# FPSInterface.net
KiCad netlist of a schematic drawn in Altium Designer
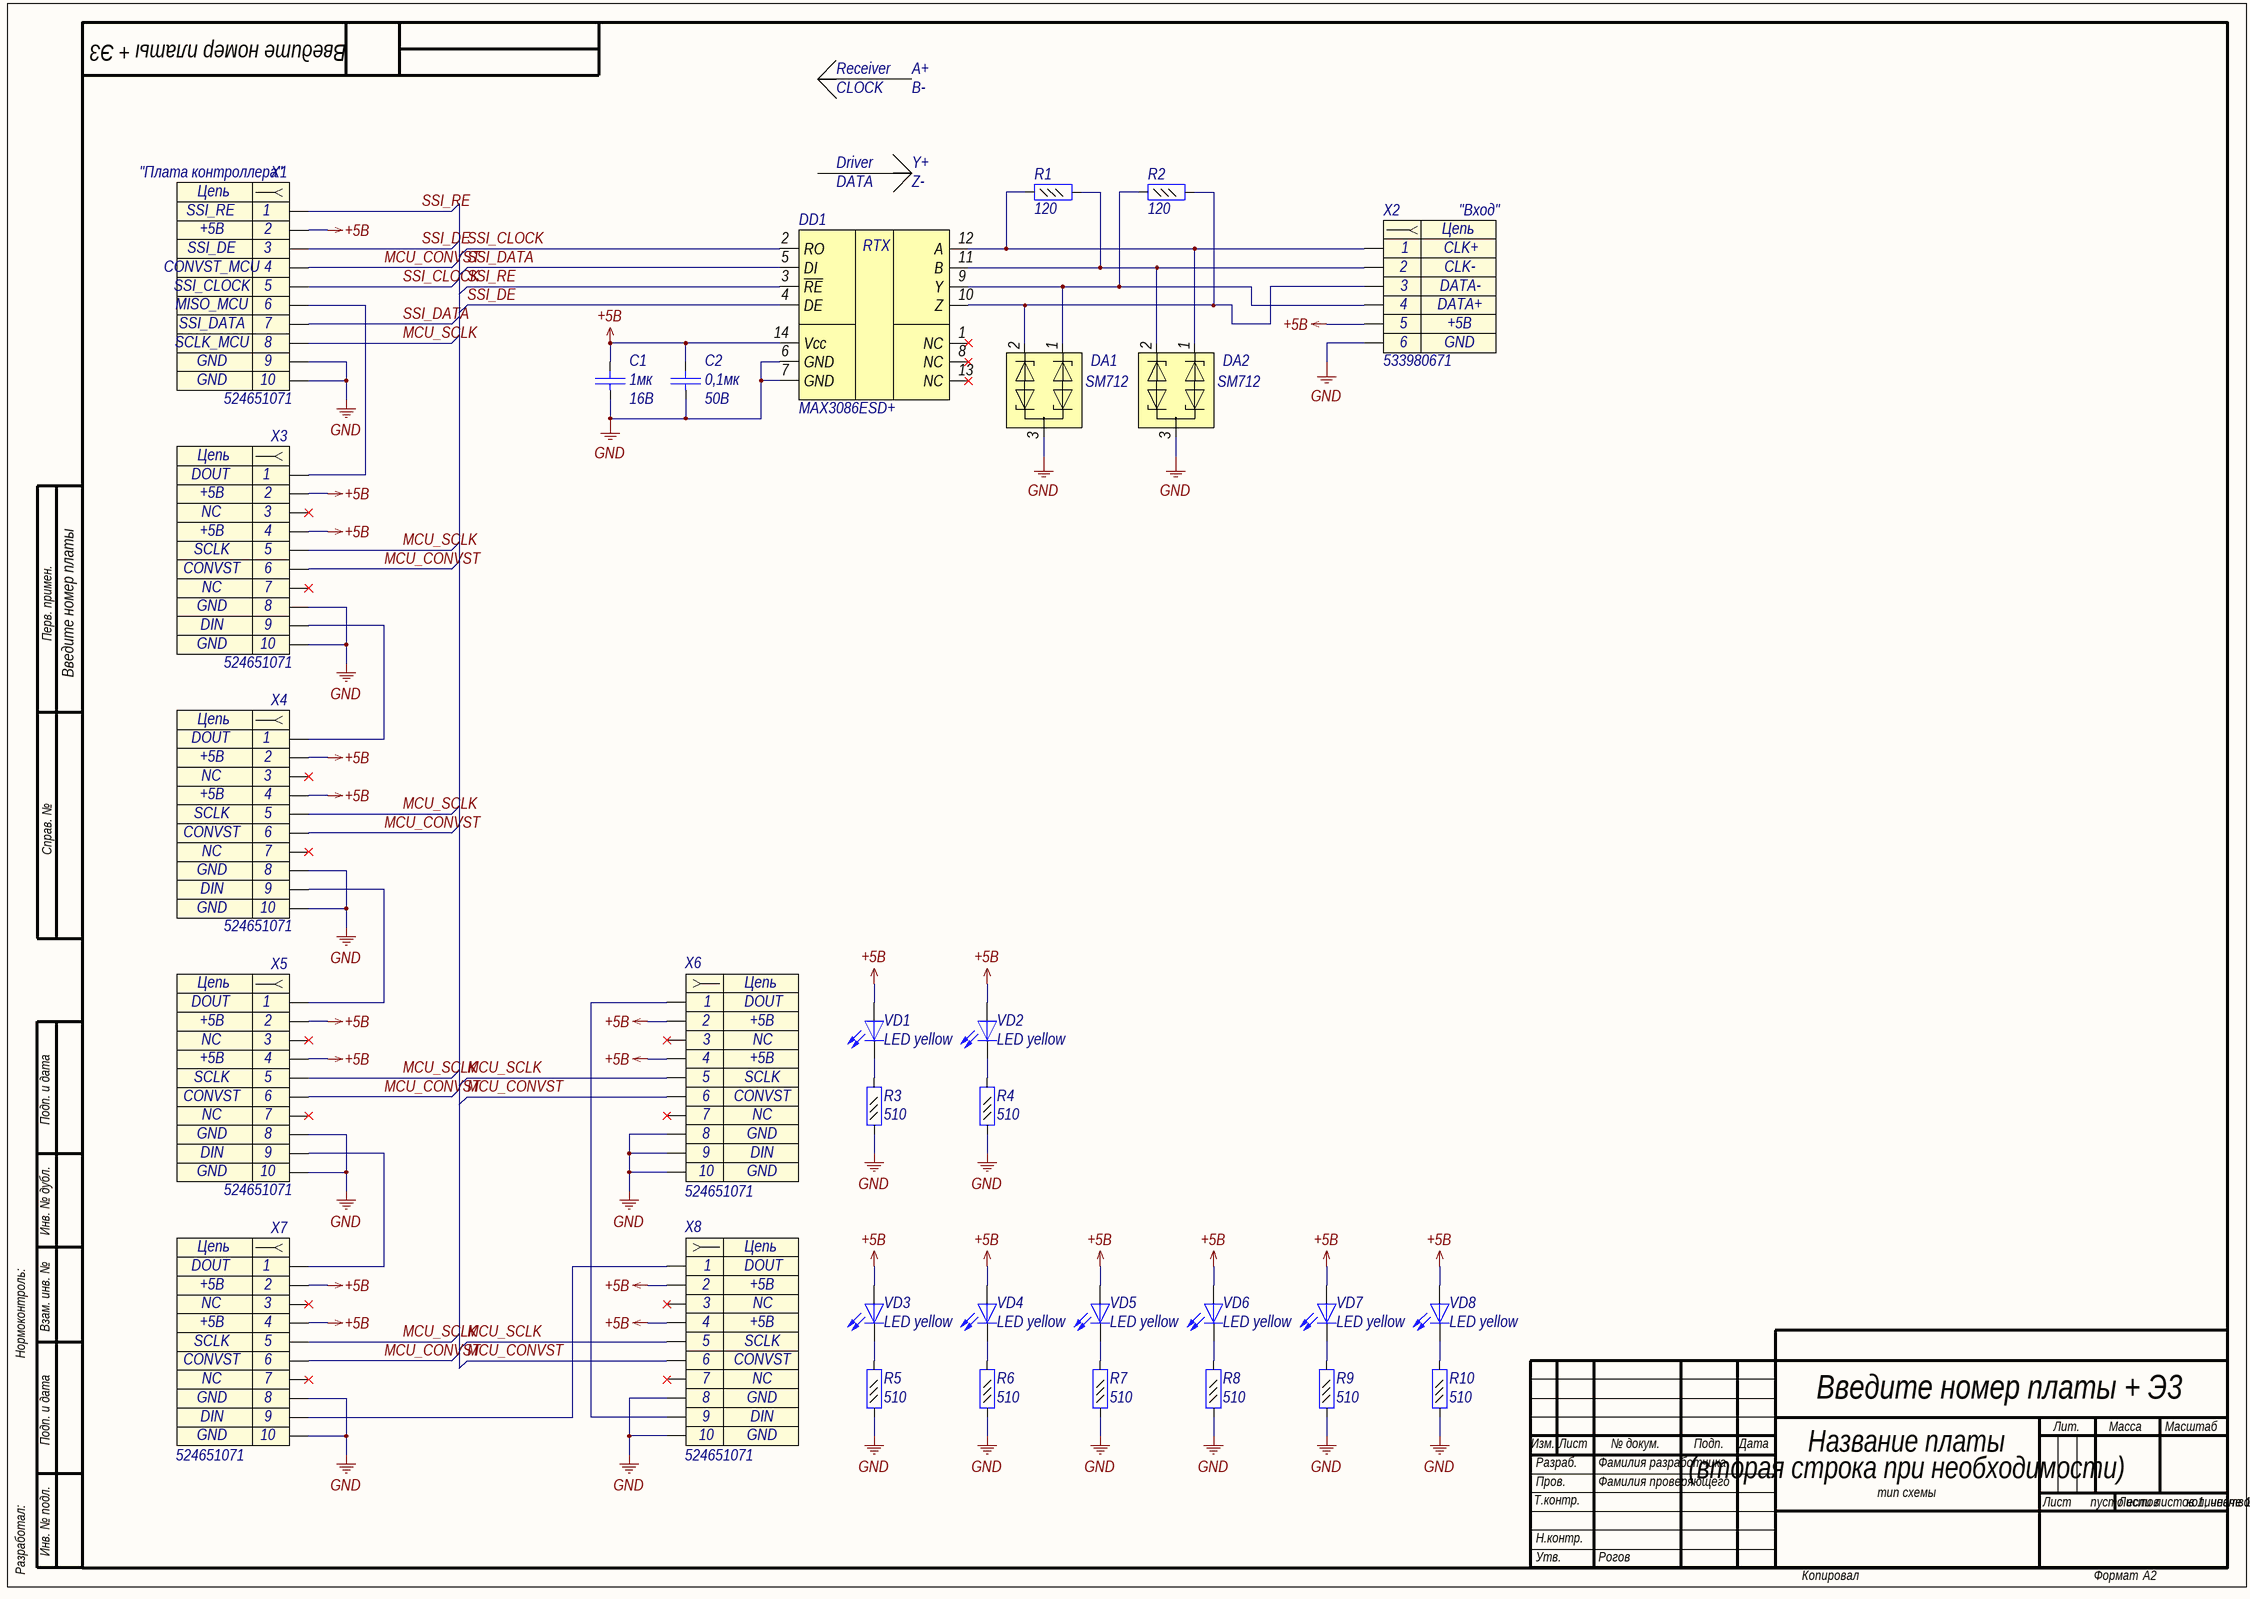
[diagram p0: FPSInterface.SchDoc]

(export (version "E")
  (design (tool "Eeschema 10.0.6"))
  (components
    (comp (ref "C1")
      (value "1мк")
      (footprint "C0603")
      (description "Конденсатор")
      (fields
        (field (name "VOLTAGE") "16B")
        (field (name "PART NUMBER") "GRM188R71C105KA12D**")
        (field (name "Comment") "Capacitor")
      )
      (libsource (lib "MOP44") (part "Capacitor"))
    )
    (comp (ref "C2")
      (value "0,1мк")
      (footprint "C0402")
      (description "Конденсатор")
      (fields
        (field (name "VOLTAGE") "50В")
        (field (name "PART NUMBER") "GRM155R71H104KE14D ")
        (field (name "Comment") "Capacitor")
      )
      (libsource (lib "MOP44") (part "Capacitor"))
    )
    (comp (ref "DA1")
      (value "SM712")
      (footprint "SOT23-3")
      (description "TVS")
      (fields (field (name "PART NUMBER") "SM712.TCT"))
      (libsource (lib "MOP44") (part "SM712"))
    )
    (comp (ref "DA2")
      (value "SM712")
      (footprint "SOT23-3")
      (description "TVS")
      (fields (field (name "PART NUMBER") "SM712.TCT"))
      (libsource (lib "MOP44") (part "SM712"))
    )
    (comp (ref "DD1")
      (value "~")
      (footprint "SO14")
      (description "Fail-Safe, High-Speed (10Mbps),  Slew-Rate-Limited RS-485/RS-422 Transceivers")
      (fields (field (name "PART NUMBER") "MAX3086ESD+"))
      (libsource (lib "MOP44") (part "MAX3086"))
    )
    (comp (ref "R1")
      (value "120")
      (footprint "R0402")
      (description "Резистор")
      (fields (field (name "PART NUMBER") "RC0402FR-07120RL") (field (name "POWER") "0,062Вт"))
      (libsource (lib "") (part "Resistor_0,062Вт_1"))
    )
    (comp (ref "R2")
      (value "120")
      (footprint "R0402")
      (description "Резистор")
      (fields (field (name "PART NUMBER") "RC0402FR-07120RL") (field (name "POWER") "0,062Вт"))
      (libsource (lib "") (part "Resistor_0,062Вт_1"))
    )
    (comp (ref "R3")
      (value "510")
      (footprint "R0402")
      (description "Резистор")
      (fields (field (name "PART NUMBER") "RC0402FR-07510RL") (field (name "POWER") "0,062Вт"))
      (libsource (lib "MOP44") (part "Resistor_0,062Вт"))
    )
    (comp (ref "R4")
      (value "510")
      (footprint "R0402")
      (description "Резистор")
      (fields (field (name "PART NUMBER") "RC0402FR-07510RL") (field (name "POWER") "0,062Вт"))
      (libsource (lib "MOP44") (part "Resistor_0,062Вт"))
    )
    (comp (ref "R5")
      (value "510")
      (footprint "R0402")
      (description "Резистор")
      (fields (field (name "PART NUMBER") "RC0402FR-07510RL") (field (name "POWER") "0,062Вт"))
      (libsource (lib "MOP44") (part "Resistor_0,062Вт"))
    )
    (comp (ref "R6")
      (value "510")
      (footprint "R0402")
      (description "Резистор")
      (fields (field (name "PART NUMBER") "RC0402FR-07510RL") (field (name "POWER") "0,062Вт"))
      (libsource (lib "MOP44") (part "Resistor_0,062Вт"))
    )
    (comp (ref "R7")
      (value "510")
      (footprint "R0402")
      (description "Резистор")
      (fields (field (name "PART NUMBER") "RC0402FR-07510RL") (field (name "POWER") "0,062Вт"))
      (libsource (lib "MOP44") (part "Resistor_0,062Вт"))
    )
    (comp (ref "R8")
      (value "510")
      (footprint "R0402")
      (description "Резистор")
      (fields (field (name "PART NUMBER") "RC0402FR-07510RL") (field (name "POWER") "0,062Вт"))
      (libsource (lib "MOP44") (part "Resistor_0,062Вт"))
    )
    (comp (ref "R9")
      (value "510")
      (footprint "R0402")
      (description "Резистор")
      (fields (field (name "PART NUMBER") "RC0402FR-07510RL") (field (name "POWER") "0,062Вт"))
      (libsource (lib "MOP44") (part "Resistor_0,062Вт"))
    )
    (comp (ref "R10")
      (value "510")
      (footprint "R0402")
      (description "Резистор")
      (fields (field (name "PART NUMBER") "RC0402FR-07510RL") (field (name "POWER") "0,062Вт"))
      (libsource (lib "MOP44") (part "Resistor_0,062Вт"))
    )
    (comp (ref "VD1")
      (value "LED")
      (footprint "L_0402_YELLOW")
      (description "Светодиод")
      (fields (field (name "PART NAME") "LED yellow") (field (name "PART NUMBER") "KPHHS-1005SYCK"))
      (libsource (lib "MOP44") (part "LED"))
    )
    (comp (ref "VD2")
      (value "LED")
      (footprint "L_0402_YELLOW")
      (description "Светодиод")
      (fields (field (name "PART NAME") "LED yellow") (field (name "PART NUMBER") "KPHHS-1005SYCK"))
      (libsource (lib "MOP44") (part "LED"))
    )
    (comp (ref "VD3")
      (value "LED")
      (footprint "L_0402_YELLOW")
      (description "Светодиод")
      (fields (field (name "PART NAME") "LED yellow") (field (name "PART NUMBER") "KPHHS-1005SYCK"))
      (libsource (lib "MOP44") (part "LED"))
    )
    (comp (ref "VD4")
      (value "LED")
      (footprint "L_0402_YELLOW")
      (description "Светодиод")
      (fields (field (name "PART NAME") "LED yellow") (field (name "PART NUMBER") "KPHHS-1005SYCK"))
      (libsource (lib "MOP44") (part "LED"))
    )
    (comp (ref "VD5")
      (value "LED")
      (footprint "L_0402_YELLOW")
      (description "Светодиод")
      (fields (field (name "PART NAME") "LED yellow") (field (name "PART NUMBER") "KPHHS-1005SYCK"))
      (libsource (lib "MOP44") (part "LED"))
    )
    (comp (ref "VD6")
      (value "LED")
      (footprint "L_0402_YELLOW")
      (description "Светодиод")
      (fields (field (name "PART NAME") "LED yellow") (field (name "PART NUMBER") "KPHHS-1005SYCK"))
      (libsource (lib "MOP44") (part "LED"))
    )
    (comp (ref "VD7")
      (value "LED")
      (footprint "L_0402_YELLOW")
      (description "Светодиод")
      (fields (field (name "PART NAME") "LED yellow") (field (name "PART NUMBER") "KPHHS-1005SYCK"))
      (libsource (lib "MOP44") (part "LED"))
    )
    (comp (ref "VD8")
      (value "LED")
      (footprint "L_0402_YELLOW")
      (description "Светодиод")
      (fields (field (name "PART NAME") "LED yellow") (field (name "PART NUMBER") "KPHHS-1005SYCK"))
      (libsource (lib "MOP44") (part "LED"))
    )
    (comp (ref "X1")
      (value "\"Плата контроллера\"")
      (footprint "SlimStack-10pin-vert-sct")
      (description "Разъем - 10 конт. розетка")
      (fields (field (name "PART NUMBER") "524651071"))
      (libsource (lib "MOP44") (part "Header_10_sct"))
    )
    (comp (ref "X2")
      (value "\"Вход\"")
      (footprint "MOLEX_533980671")
      (description "Разъем - 6 конт. розетка")
      (fields (field (name "PART NUMBER") "533980671"))
      (libsource (lib "MOP44") (part "Header_6_sct"))
    )
    (comp (ref "X3")
      (value "Header_10_sct")
      (footprint "SlimStack-10pin-vert-sct")
      (description "Разъем - 10 конт. розетка")
      (fields (field (name "PART NUMBER") "524651071"))
      (libsource (lib "MOP44") (part "Header_10_sct"))
    )
    (comp (ref "X4")
      (value "Header_10_sct")
      (footprint "SlimStack-10pin-vert-sct")
      (description "Разъем - 10 конт. розетка")
      (fields (field (name "PART NUMBER") "524651071"))
      (libsource (lib "MOP44") (part "Header_10_sct"))
    )
    (comp (ref "X5")
      (value "Header_10_sct")
      (footprint "SlimStack-10pin-vert-sct")
      (description "Разъем - 10 конт. розетка")
      (fields (field (name "PART NUMBER") "524651071"))
      (libsource (lib "MOP44") (part "Header_10_sct"))
    )
    (comp (ref "X6")
      (value "Header_10_sct")
      (footprint "SlimStack-10pin-vert-sct")
      (description "Разъем - 10 конт. розетка")
      (fields (field (name "PART NUMBER") "524651071"))
      (libsource (lib "") (part "Header_10_sct_1"))
    )
    (comp (ref "X7")
      (value "Header_10_sct")
      (footprint "SlimStack-10pin-vert-sct")
      (description "Разъем - 10 конт. розетка")
      (fields (field (name "PART NUMBER") "524651071"))
      (libsource (lib "MOP44") (part "Header_10_sct"))
    )
    (comp (ref "X8")
      (value "Header_10_sct")
      (footprint "SlimStack-10pin-vert-sct")
      (description "Разъем - 10 конт. розетка")
      (fields (field (name "PART NUMBER") "524651071"))
      (libsource (lib "") (part "Header_10_sct_1"))
    )
  )
  (nets
    (net (code "1") (name "+5B") (class "Default")
      (node (ref "C1") (pin "2") (pinfunction "2_2") (pintype "passive"))
      (node (ref "C2") (pin "2") (pinfunction "2_2") (pintype "passive"))
      (node (ref "DD1") (pin "14") (pinfunction "Vcc_14") (pintype "passive"))
      (node (ref "VD1") (pin "2") (pinfunction "A_2") (pintype "passive"))
      (node (ref "VD2") (pin "2") (pinfunction "A_2") (pintype "passive"))
      (node (ref "VD3") (pin "2") (pinfunction "A_2") (pintype "passive"))
      (node (ref "VD4") (pin "2") (pinfunction "A_2") (pintype "passive"))
      (node (ref "VD5") (pin "2") (pinfunction "A_2") (pintype "passive"))
      (node (ref "VD6") (pin "2") (pinfunction "A_2") (pintype "passive"))
      (node (ref "VD7") (pin "2") (pinfunction "A_2") (pintype "passive"))
      (node (ref "VD8") (pin "2") (pinfunction "A_2") (pintype "passive"))
      (node (ref "X1") (pin "2") (pinfunction "2_2") (pintype "passive"))
      (node (ref "X2") (pin "5") (pinfunction "5_5") (pintype "passive"))
      (node (ref "X3") (pin "2") (pinfunction "2_2") (pintype "passive"))
      (node (ref "X3") (pin "4") (pinfunction "4_4") (pintype "passive"))
      (node (ref "X4") (pin "2") (pinfunction "2_2") (pintype "passive"))
      (node (ref "X4") (pin "4") (pinfunction "4_4") (pintype "passive"))
      (node (ref "X5") (pin "2") (pinfunction "2_2") (pintype "passive"))
      (node (ref "X5") (pin "4") (pinfunction "4_4") (pintype "passive"))
      (node (ref "X6") (pin "2") (pinfunction "2_2") (pintype "passive"))
      (node (ref "X6") (pin "4") (pinfunction "4_4") (pintype "passive"))
      (node (ref "X7") (pin "2") (pinfunction "2_2") (pintype "passive"))
      (node (ref "X7") (pin "4") (pinfunction "4_4") (pintype "passive"))
      (node (ref "X8") (pin "2") (pinfunction "2_2") (pintype "passive"))
      (node (ref "X8") (pin "4") (pinfunction "4_4") (pintype "passive"))
    )
    (net (code "2") (name "/MCU_CONVST") (class "Default")
      (node (ref "X1") (pin "4") (pinfunction "4_4") (pintype "passive"))
      (node (ref "X3") (pin "6") (pinfunction "6_6") (pintype "passive"))
      (node (ref "X4") (pin "6") (pinfunction "6_6") (pintype "passive"))
      (node (ref "X5") (pin "6") (pinfunction "6_6") (pintype "passive"))
      (node (ref "X6") (pin "6") (pinfunction "6_6") (pintype "passive"))
      (node (ref "X7") (pin "6") (pinfunction "6_6") (pintype "passive"))
      (node (ref "X8") (pin "6") (pinfunction "6_6") (pintype "passive"))
    )
    (net (code "3") (name "/MCU_SCLK") (class "Default")
      (node (ref "X1") (pin "8") (pinfunction "8_8") (pintype "passive"))
      (node (ref "X3") (pin "5") (pinfunction "5_5") (pintype "passive"))
      (node (ref "X4") (pin "5") (pinfunction "5_5") (pintype "passive"))
      (node (ref "X5") (pin "5") (pinfunction "5_5") (pintype "passive"))
      (node (ref "X6") (pin "5") (pinfunction "5_5") (pintype "passive"))
      (node (ref "X7") (pin "5") (pinfunction "5_5") (pintype "passive"))
      (node (ref "X8") (pin "5") (pinfunction "5_5") (pintype "passive"))
    )
    (net (code "4") (name "/SSI_CLOCK") (class "Default")
      (node (ref "DD1") (pin "2") (pinfunction "RO_2") (pintype "passive"))
      (node (ref "X1") (pin "5") (pinfunction "5_5") (pintype "passive"))
    )
    (net (code "5") (name "/SSI_DATA") (class "Default")
      (node (ref "DD1") (pin "5") (pinfunction "DI_5") (pintype "passive"))
      (node (ref "X1") (pin "7") (pinfunction "7_7") (pintype "passive"))
    )
    (net (code "6") (name "/SSI_DE") (class "Default")
      (node (ref "DD1") (pin "4") (pinfunction "DE_4") (pintype "passive"))
      (node (ref "X1") (pin "3") (pinfunction "3_3") (pintype "passive"))
    )
    (net (code "7") (name "/SSI_RE") (class "Default")
      (node (ref "DD1") (pin "3") (pinfunction "~{RE}_3") (pintype "passive"))
      (node (ref "X1") (pin "1") (pinfunction "1_1") (pintype "passive"))
    )
    (net (code "8") (name "GND") (class "Default")
      (node (ref "C1") (pin "1") (pinfunction "1_1") (pintype "passive"))
      (node (ref "C2") (pin "1") (pinfunction "1_1") (pintype "passive"))
      (node (ref "DA1") (pin "3") (pintype "passive"))
      (node (ref "DA2") (pin "3") (pintype "passive"))
      (node (ref "DD1") (pin "6") (pinfunction "GND_6") (pintype "passive"))
      (node (ref "DD1") (pin "7") (pinfunction "GND_7") (pintype "passive"))
      (node (ref "R10") (pin "1") (pinfunction "1_1") (pintype "passive"))
      (node (ref "R3") (pin "1") (pinfunction "1_1") (pintype "passive"))
      (node (ref "R4") (pin "1") (pinfunction "1_1") (pintype "passive"))
      (node (ref "R5") (pin "1") (pinfunction "1_1") (pintype "passive"))
      (node (ref "R6") (pin "1") (pinfunction "1_1") (pintype "passive"))
      (node (ref "R7") (pin "1") (pinfunction "1_1") (pintype "passive"))
      (node (ref "R8") (pin "1") (pinfunction "1_1") (pintype "passive"))
      (node (ref "R9") (pin "1") (pinfunction "1_1") (pintype "passive"))
      (node (ref "X1") (pin "10") (pinfunction "10_10") (pintype "passive"))
      (node (ref "X1") (pin "9") (pinfunction "9_9") (pintype "passive"))
      (node (ref "X2") (pin "6") (pinfunction "6_6") (pintype "passive"))
      (node (ref "X3") (pin "10") (pinfunction "10_10") (pintype "passive"))
      (node (ref "X3") (pin "8") (pinfunction "8_8") (pintype "passive"))
      (node (ref "X4") (pin "10") (pinfunction "10_10") (pintype "passive"))
      (node (ref "X4") (pin "8") (pinfunction "8_8") (pintype "passive"))
      (node (ref "X5") (pin "10") (pinfunction "10_10") (pintype "passive"))
      (node (ref "X5") (pin "8") (pinfunction "8_8") (pintype "passive"))
      (node (ref "X6") (pin "10") (pinfunction "10_10") (pintype "passive"))
      (node (ref "X6") (pin "8") (pinfunction "8_8") (pintype "passive"))
      (node (ref "X6") (pin "9") (pinfunction "9_9") (pintype "passive"))
      (node (ref "X7") (pin "10") (pinfunction "10_10") (pintype "passive"))
      (node (ref "X7") (pin "8") (pinfunction "8_8") (pintype "passive"))
      (node (ref "X8") (pin "10") (pinfunction "10_10") (pintype "passive"))
      (node (ref "X8") (pin "8") (pinfunction "8_8") (pintype "passive"))
    )
    (net (code "9") (name "Net-(DA1-1)") (class "Default")
      (node (ref "DA1") (pin "2") (pinfunction "1_2") (pintype "passive"))
      (node (ref "DD1") (pin "10") (pinfunction "Z_10") (pintype "passive"))
      (node (ref "R2") (pin "2") (pinfunction "2_2") (pintype "passive"))
      (node (ref "X2") (pin "3") (pinfunction "3_3") (pintype "passive"))
    )
    (net (code "10") (name "Net-(DA2-1)") (class "Default")
      (node (ref "DA2") (pin "2") (pinfunction "1_2") (pintype "passive"))
      (node (ref "DD1") (pin "11") (pinfunction "B_11") (pintype "passive"))
      (node (ref "R1") (pin "2") (pinfunction "2_2") (pintype "passive"))
      (node (ref "X2") (pin "2") (pinfunction "2_2") (pintype "passive"))
    )
    (net (code "11") (name "Net-(DD1-A)") (class "Default")
      (node (ref "DA2") (pin "1") (pintype "passive"))
      (node (ref "DD1") (pin "12") (pinfunction "A_12") (pintype "passive"))
      (node (ref "R1") (pin "1") (pinfunction "1_1") (pintype "passive"))
      (node (ref "X2") (pin "1") (pinfunction "1_1") (pintype "passive"))
    )
    (net (code "12") (name "Net-(DD1-Y)") (class "Default")
      (node (ref "DA1") (pin "1") (pintype "passive"))
      (node (ref "DD1") (pin "9") (pinfunction "Y_9") (pintype "passive"))
      (node (ref "R2") (pin "1") (pinfunction "1_1") (pintype "passive"))
      (node (ref "X2") (pin "4") (pinfunction "4_4") (pintype "passive"))
    )
    (net (code "13") (name "Net-(VD1-K)") (class "Default")
      (node (ref "R3") (pin "2") (pinfunction "2_2") (pintype "passive"))
      (node (ref "VD1") (pin "1") (pinfunction "K_1") (pintype "passive"))
    )
    (net (code "14") (name "Net-(VD2-K)") (class "Default")
      (node (ref "R4") (pin "2") (pinfunction "2_2") (pintype "passive"))
      (node (ref "VD2") (pin "1") (pinfunction "K_1") (pintype "passive"))
    )
    (net (code "15") (name "Net-(VD3-K)") (class "Default")
      (node (ref "R5") (pin "2") (pinfunction "2_2") (pintype "passive"))
      (node (ref "VD3") (pin "1") (pinfunction "K_1") (pintype "passive"))
    )
    (net (code "16") (name "Net-(VD4-K)") (class "Default")
      (node (ref "R6") (pin "2") (pinfunction "2_2") (pintype "passive"))
      (node (ref "VD4") (pin "1") (pinfunction "K_1") (pintype "passive"))
    )
    (net (code "17") (name "Net-(VD5-K)") (class "Default")
      (node (ref "R7") (pin "2") (pinfunction "2_2") (pintype "passive"))
      (node (ref "VD5") (pin "1") (pinfunction "K_1") (pintype "passive"))
    )
    (net (code "18") (name "Net-(VD6-K)") (class "Default")
      (node (ref "R8") (pin "2") (pinfunction "2_2") (pintype "passive"))
      (node (ref "VD6") (pin "1") (pinfunction "K_1") (pintype "passive"))
    )
    (net (code "19") (name "Net-(VD7-K)") (class "Default")
      (node (ref "R9") (pin "2") (pinfunction "2_2") (pintype "passive"))
      (node (ref "VD7") (pin "1") (pinfunction "K_1") (pintype "passive"))
    )
    (net (code "20") (name "Net-(VD8-K)") (class "Default")
      (node (ref "R10") (pin "2") (pinfunction "2_2") (pintype "passive"))
      (node (ref "VD8") (pin "1") (pinfunction "K_1") (pintype "passive"))
    )
    (net (code "21") (name "Net-(X1-Pad6)") (class "Default")
      (node (ref "X1") (pin "6") (pinfunction "6_6") (pintype "passive"))
      (node (ref "X3") (pin "1") (pinfunction "1_1") (pintype "passive"))
    )
    (net (code "22") (name "Net-(X3-Pad9)") (class "Default")
      (node (ref "X3") (pin "9") (pinfunction "9_9") (pintype "passive"))
      (node (ref "X4") (pin "1") (pinfunction "1_1") (pintype "passive"))
    )
    (net (code "23") (name "Net-(X4-Pad9)") (class "Default")
      (node (ref "X4") (pin "9") (pinfunction "9_9") (pintype "passive"))
      (node (ref "X5") (pin "1") (pinfunction "1_1") (pintype "passive"))
    )
    (net (code "24") (name "Net-(X5-Pad9)") (class "Default")
      (node (ref "X5") (pin "9") (pinfunction "9_9") (pintype "passive"))
      (node (ref "X7") (pin "1") (pinfunction "1_1") (pintype "passive"))
    )
    (net (code "25") (name "Net-(X6-Pad1)") (class "Default")
      (node (ref "X6") (pin "1") (pinfunction "1_1") (pintype "passive"))
      (node (ref "X8") (pin "9") (pinfunction "9_9") (pintype "passive"))
    )
    (net (code "26") (name "Net-(X7-Pad9)") (class "Default")
      (node (ref "X7") (pin "9") (pinfunction "9_9") (pintype "passive"))
      (node (ref "X8") (pin "1") (pinfunction "1_1") (pintype "passive"))
    )
    (net (code "27") (name "unconnected-(DD1-NC-Pad1)") (class "Default")
      (node (ref "DD1") (pin "1") (pinfunction "NC_1") (pintype "passive+no_connect"))
    )
    (net (code "28") (name "unconnected-(DD1-NC-Pad8)") (class "Default")
      (node (ref "DD1") (pin "8") (pinfunction "NC_8") (pintype "passive+no_connect"))
    )
    (net (code "29") (name "unconnected-(DD1-NC-Pad13)") (class "Default")
      (node (ref "DD1") (pin "13") (pinfunction "NC_13") (pintype "passive+no_connect"))
    )
    (net (code "30") (name "unconnected-(X3-Pad3)") (class "Default")
      (node (ref "X3") (pin "3") (pinfunction "3_3") (pintype "passive+no_connect"))
    )
    (net (code "31") (name "unconnected-(X3-Pad7)") (class "Default")
      (node (ref "X3") (pin "7") (pinfunction "7_7") (pintype "passive+no_connect"))
    )
    (net (code "32") (name "unconnected-(X4-Pad3)") (class "Default")
      (node (ref "X4") (pin "3") (pinfunction "3_3") (pintype "passive+no_connect"))
    )
    (net (code "33") (name "unconnected-(X4-Pad7)") (class "Default")
      (node (ref "X4") (pin "7") (pinfunction "7_7") (pintype "passive+no_connect"))
    )
    (net (code "34") (name "unconnected-(X5-Pad3)") (class "Default")
      (node (ref "X5") (pin "3") (pinfunction "3_3") (pintype "passive+no_connect"))
    )
    (net (code "35") (name "unconnected-(X5-Pad7)") (class "Default")
      (node (ref "X5") (pin "7") (pinfunction "7_7") (pintype "passive+no_connect"))
    )
    (net (code "36") (name "unconnected-(X6-Pad3)") (class "Default")
      (node (ref "X6") (pin "3") (pinfunction "3_3") (pintype "passive+no_connect"))
    )
    (net (code "37") (name "unconnected-(X6-Pad7)") (class "Default")
      (node (ref "X6") (pin "7") (pinfunction "7_7") (pintype "passive+no_connect"))
    )
    (net (code "38") (name "unconnected-(X7-Pad3)") (class "Default")
      (node (ref "X7") (pin "3") (pinfunction "3_3") (pintype "passive+no_connect"))
    )
    (net (code "39") (name "unconnected-(X7-Pad7)") (class "Default")
      (node (ref "X7") (pin "7") (pinfunction "7_7") (pintype "passive+no_connect"))
    )
    (net (code "40") (name "unconnected-(X8-Pad3)") (class "Default")
      (node (ref "X8") (pin "3") (pinfunction "3_3") (pintype "passive+no_connect"))
    )
    (net (code "41") (name "unconnected-(X8-Pad7)") (class "Default")
      (node (ref "X8") (pin "7") (pinfunction "7_7") (pintype "passive+no_connect"))
    )
  )
)
